# tr2.net
KiCad netlist of a schematic drawn in EAGLE
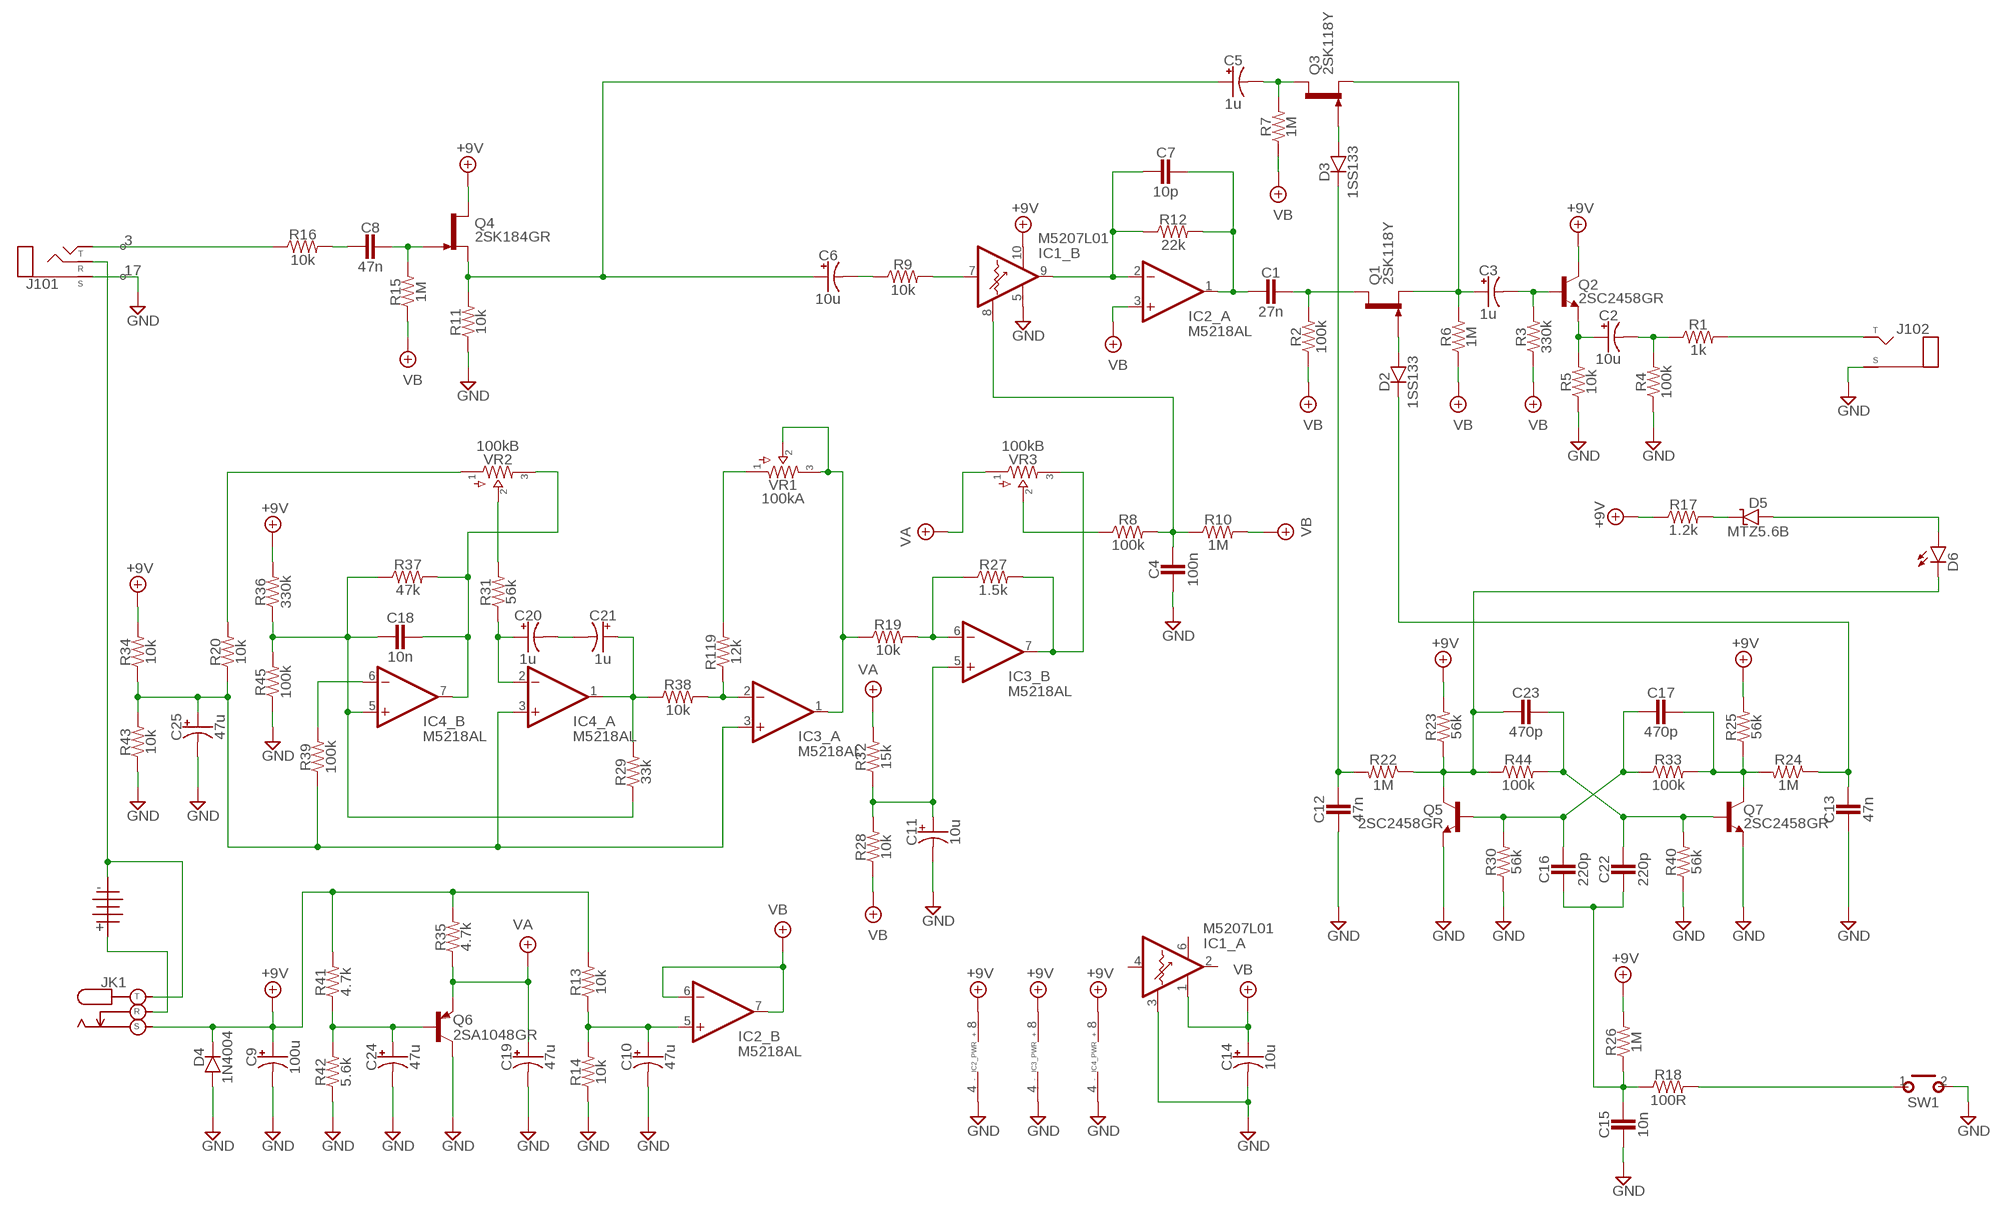
[diagram p0: schematic, sheet 1]

(export (version "E")
  (design (tool "Eeschema 10.0.6"))
  (components
    (comp (ref "1101")
      (value "BATTERY")
      (footprint "eagle-import:TWO_PADS")
      (libsource (lib "eagle-import") (part "BATTERY"))
    )
    (comp (ref "C1")
      (value "27n")
      (footprint "eagle-import:BOX_SMALL")
      (libsource (lib "eagle-import") (part "CER/FILMBOX.1"))
    )
    (comp (ref "C2")
      (value "10u")
      (footprint "eagle-import:040_020")
      (libsource (lib "eagle-import") (part "0400"))
    )
    (comp (ref "C3")
      (value "1u")
      (footprint "eagle-import:040_020")
      (libsource (lib "eagle-import") (part "0400"))
    )
    (comp (ref "C4")
      (value "100n")
      (footprint "eagle-import:BOX_SMALL")
      (libsource (lib "eagle-import") (part "CER/FILMBOX.1"))
    )
    (comp (ref "C5")
      (value "1u")
      (footprint "eagle-import:040_020")
      (libsource (lib "eagle-import") (part "0400"))
    )
    (comp (ref "C6")
      (value "10u")
      (footprint "eagle-import:040_020")
      (libsource (lib "eagle-import") (part "0400"))
    )
    (comp (ref "C7")
      (value "10p")
      (footprint "eagle-import:BOX_SMALL")
      (libsource (lib "eagle-import") (part "CER/FILMBOX.1"))
    )
    (comp (ref "C8")
      (value "47n")
      (footprint "eagle-import:BOX_SMALL")
      (libsource (lib "eagle-import") (part "CER/FILMBOX.1"))
    )
    (comp (ref "C9")
      (value "100u")
      (footprint "eagle-import:040_020")
      (libsource (lib "eagle-import") (part "0400"))
    )
    (comp (ref "C10")
      (value "47u")
      (footprint "eagle-import:040_020")
      (libsource (lib "eagle-import") (part "0400"))
    )
    (comp (ref "C11")
      (value "10u")
      (footprint "eagle-import:040_020")
      (libsource (lib "eagle-import") (part "0400"))
    )
    (comp (ref "C12")
      (value "47n")
      (footprint "eagle-import:BOX_SMALL")
      (libsource (lib "eagle-import") (part "CER/FILMBOX.1"))
    )
    (comp (ref "C13")
      (value "47n")
      (footprint "eagle-import:BOX_SMALL")
      (libsource (lib "eagle-import") (part "CER/FILMBOX.1"))
    )
    (comp (ref "C14")
      (value "10u")
      (footprint "eagle-import:040_020")
      (libsource (lib "eagle-import") (part "0400"))
    )
    (comp (ref "C15")
      (value "10n")
      (footprint "eagle-import:BOX_SMALL")
      (libsource (lib "eagle-import") (part "CER/FILMBOX.1"))
    )
    (comp (ref "C16")
      (value "220p")
      (footprint "eagle-import:BOX_SMALL")
      (libsource (lib "eagle-import") (part "CER/FILMBOX.1"))
    )
    (comp (ref "C17")
      (value "470p")
      (footprint "eagle-import:BOX_SMALL")
      (libsource (lib "eagle-import") (part "CER/FILMBOX.1"))
    )
    (comp (ref "C18")
      (value "10n")
      (footprint "eagle-import:BOX_SMALL")
      (libsource (lib "eagle-import") (part "CER/FILMBOX.1"))
    )
    (comp (ref "C19")
      (value "47u")
      (footprint "eagle-import:040_020")
      (libsource (lib "eagle-import") (part "0400"))
    )
    (comp (ref "C20")
      (value "1u")
      (footprint "eagle-import:040_020")
      (libsource (lib "eagle-import") (part "0400"))
    )
    (comp (ref "C21")
      (value "1u")
      (footprint "eagle-import:040_020")
      (libsource (lib "eagle-import") (part "0400"))
    )
    (comp (ref "C22")
      (value "220p")
      (footprint "eagle-import:BOX_SMALL")
      (libsource (lib "eagle-import") (part "CER/FILMBOX.1"))
    )
    (comp (ref "C23")
      (value "470p")
      (footprint "eagle-import:BOX_SMALL")
      (libsource (lib "eagle-import") (part "CER/FILMBOX.1"))
    )
    (comp (ref "C24")
      (value "47u")
      (footprint "eagle-import:040_020")
      (libsource (lib "eagle-import") (part "0400"))
    )
    (comp (ref "C25")
      (value "47u")
      (footprint "eagle-import:040_020")
      (libsource (lib "eagle-import") (part "0400"))
    )
    (comp (ref "D2")
      (value "1SS133")
      (footprint "eagle-import:DO35-2")
      (libsource (lib "eagle-import") (part "DO35.2"))
    )
    (comp (ref "D3")
      (value "1SS133")
      (footprint "eagle-import:DO35-2")
      (libsource (lib "eagle-import") (part "DO35.2"))
    )
    (comp (ref "D4")
      (value "1N4004")
      (footprint "eagle-import:DO35-2")
      (libsource (lib "eagle-import") (part "DO35.2"))
    )
    (comp (ref "D5")
      (value "MTZ5.6B")
      (footprint "eagle-import:DO41-2")
      (libsource (lib "eagle-import") (part "ZENER.2"))
    )
    (comp (ref "D6")
      (value "LN-28RP")
      (footprint "eagle-import:3MM_D")
      (libsource (lib "eagle-import") (part "LED"))
    )
    (comp (ref "IC1")
      (value "M5207L01")
      (footprint "eagle-import:SIL10")
      (libsource (lib "eagle-import") (part "M5207L01"))
    )
    (comp (ref "IC2")
      (value "M5218AL")
      (footprint "eagle-import:DIL0")
      (libsource (lib "eagle-import") (part "DUALTH"))
    )
    (comp (ref "IC3")
      (value "M5218AL")
      (footprint "eagle-import:DIL0")
      (libsource (lib "eagle-import") (part "DUALTH"))
    )
    (comp (ref "IC4")
      (value "M5218AL")
      (footprint "eagle-import:DIL0")
      (libsource (lib "eagle-import") (part "DUALTH"))
    )
    (comp (ref "J101")
      (value "STEREO3PADS")
      (footprint "eagle-import:THREEPADS")
      (libsource (lib "eagle-import") (part "STEREO3PADS"))
    )
    (comp (ref "J102")
      (value "MONO")
      (footprint "eagle-import:TWO_PADS")
      (libsource (lib "eagle-import") (part "MONO"))
    )
    (comp (ref "JK1")
      (value "DC_KOBICONN")
      (footprint "eagle-import:DC_KOBICONN")
      (libsource (lib "eagle-import") (part "DC_KOBICONN"))
    )
    (comp (ref "Q1")
      (value "2SK118Y")
      (footprint "eagle-import:TO92-")
      (libsource (lib "eagle-import") (part "2N3819TO-92S"))
    )
    (comp (ref "Q2")
      (value "2SC2458GR")
      (footprint "eagle-import:TO92-")
      (libsource (lib "eagle-import") (part "2SC828A"))
    )
    (comp (ref "Q3")
      (value "2SK118Y")
      (footprint "eagle-import:TO92-")
      (libsource (lib "eagle-import") (part "2N3819TO-92S"))
    )
    (comp (ref "Q4")
      (value "2SK184GR")
      (footprint "eagle-import:TO92-")
      (libsource (lib "eagle-import") (part "2N3819TO-92S"))
    )
    (comp (ref "Q5")
      (value "2SC2458GR")
      (footprint "eagle-import:TO92-")
      (libsource (lib "eagle-import") (part "2SC828A"))
    )
    (comp (ref "Q6")
      (value "2SA1048GR")
      (footprint "eagle-import:TO92-")
      (libsource (lib "eagle-import") (part "2N3906-"))
    )
    (comp (ref "Q7")
      (value "2SC2458GR")
      (footprint "eagle-import:TO92-")
      (libsource (lib "eagle-import") (part "2SC828A"))
    )
    (comp (ref "R1")
      (value "1k")
      (footprint "eagle-import:R0207_3")
      (libsource (lib "eagle-import") (part "R_.3B"))
    )
    (comp (ref "R2")
      (value "100k")
      (footprint "eagle-import:R0207_3")
      (libsource (lib "eagle-import") (part "R_.3B"))
    )
    (comp (ref "R3")
      (value "330k")
      (footprint "eagle-import:R0207_3")
      (libsource (lib "eagle-import") (part "R_.3B"))
    )
    (comp (ref "R4")
      (value "100k")
      (footprint "eagle-import:R0207_3")
      (libsource (lib "eagle-import") (part "R_.3B"))
    )
    (comp (ref "R5")
      (value "10k")
      (footprint "eagle-import:R0207_3")
      (libsource (lib "eagle-import") (part "R_.3B"))
    )
    (comp (ref "R6")
      (value "1M")
      (footprint "eagle-import:R0207_3")
      (libsource (lib "eagle-import") (part "R_.3B"))
    )
    (comp (ref "R7")
      (value "1M")
      (footprint "eagle-import:R0207_3")
      (libsource (lib "eagle-import") (part "R_.3B"))
    )
    (comp (ref "R8")
      (value "100k")
      (footprint "eagle-import:R0207_3")
      (libsource (lib "eagle-import") (part "R_.3B"))
    )
    (comp (ref "R9")
      (value "10k")
      (footprint "eagle-import:R0207_3")
      (libsource (lib "eagle-import") (part "R_.3B"))
    )
    (comp (ref "R10")
      (value "1M")
      (footprint "eagle-import:R0207_3")
      (libsource (lib "eagle-import") (part "R_.3B"))
    )
    (comp (ref "R11")
      (value "10k")
      (footprint "eagle-import:R0207_3")
      (libsource (lib "eagle-import") (part "R_.3B"))
    )
    (comp (ref "R12")
      (value "22k")
      (footprint "eagle-import:R0207_3")
      (libsource (lib "eagle-import") (part "R_.3B"))
    )
    (comp (ref "R13")
      (value "10k")
      (footprint "eagle-import:R0207_3")
      (libsource (lib "eagle-import") (part "R_.3B"))
    )
    (comp (ref "R14")
      (value "10k")
      (footprint "eagle-import:R0207_3")
      (libsource (lib "eagle-import") (part "R_.3B"))
    )
    (comp (ref "R15")
      (value "1M")
      (footprint "eagle-import:R0207_3")
      (libsource (lib "eagle-import") (part "R_.3B"))
    )
    (comp (ref "R16")
      (value "10k")
      (footprint "eagle-import:R0207_3")
      (libsource (lib "eagle-import") (part "R_.3B"))
    )
    (comp (ref "R17")
      (value "1.2k")
      (footprint "eagle-import:R0207_3")
      (libsource (lib "eagle-import") (part "R_.3B"))
    )
    (comp (ref "R18")
      (value "100R")
      (footprint "eagle-import:R0207_3")
      (libsource (lib "eagle-import") (part "R_.3B"))
    )
    (comp (ref "R19")
      (value "10k")
      (footprint "eagle-import:R0207_3")
      (libsource (lib "eagle-import") (part "R_.3B"))
    )
    (comp (ref "R20")
      (value "10k")
      (footprint "eagle-import:R0207_3")
      (libsource (lib "eagle-import") (part "R_.3B"))
    )
    (comp (ref "R22")
      (value "1M")
      (footprint "eagle-import:R0207_3")
      (libsource (lib "eagle-import") (part "R_.3B"))
    )
    (comp (ref "R23")
      (value "56k")
      (footprint "eagle-import:R0207_3")
      (libsource (lib "eagle-import") (part "R_.3B"))
    )
    (comp (ref "R24")
      (value "1M")
      (footprint "eagle-import:R0207_3")
      (libsource (lib "eagle-import") (part "R_.3B"))
    )
    (comp (ref "R25")
      (value "56k")
      (footprint "eagle-import:R0207_3")
      (libsource (lib "eagle-import") (part "R_.3B"))
    )
    (comp (ref "R26")
      (value "1M")
      (footprint "eagle-import:R0207_3")
      (libsource (lib "eagle-import") (part "R_.3B"))
    )
    (comp (ref "R27")
      (value "1.5k")
      (footprint "eagle-import:R0207_3")
      (libsource (lib "eagle-import") (part "R_.3B"))
    )
    (comp (ref "R28")
      (value "10k")
      (footprint "eagle-import:R0207_3")
      (libsource (lib "eagle-import") (part "R_.3B"))
    )
    (comp (ref "R29")
      (value "33k")
      (footprint "eagle-import:R0207_3")
      (libsource (lib "eagle-import") (part "R_.3B"))
    )
    (comp (ref "R30")
      (value "56k")
      (footprint "eagle-import:R0207_3")
      (libsource (lib "eagle-import") (part "R_.3B"))
    )
    (comp (ref "R31")
      (value "56k")
      (footprint "eagle-import:R0207_3")
      (libsource (lib "eagle-import") (part "R_.3B"))
    )
    (comp (ref "R32")
      (value "15k")
      (footprint "eagle-import:R0207_3")
      (libsource (lib "eagle-import") (part "R_.3B"))
    )
    (comp (ref "R33")
      (value "100k")
      (footprint "eagle-import:R0207_3")
      (libsource (lib "eagle-import") (part "R_.3B"))
    )
    (comp (ref "R34")
      (value "10k")
      (footprint "eagle-import:R0207_3")
      (libsource (lib "eagle-import") (part "R_.3B"))
    )
    (comp (ref "R35")
      (value "4.7k")
      (footprint "eagle-import:R0207_3")
      (libsource (lib "eagle-import") (part "R_.3B"))
    )
    (comp (ref "R36")
      (value "330k")
      (footprint "eagle-import:R0207_3")
      (libsource (lib "eagle-import") (part "R_.3B"))
    )
    (comp (ref "R37")
      (value "47k")
      (footprint "eagle-import:R0207_3")
      (libsource (lib "eagle-import") (part "R_.3B"))
    )
    (comp (ref "R38")
      (value "10k")
      (footprint "eagle-import:R0207_3")
      (libsource (lib "eagle-import") (part "R_.3B"))
    )
    (comp (ref "R39")
      (value "100k")
      (footprint "eagle-import:R0207_3")
      (libsource (lib "eagle-import") (part "R_.3B"))
    )
    (comp (ref "R40")
      (value "56k")
      (footprint "eagle-import:R0207_3")
      (libsource (lib "eagle-import") (part "R_.3B"))
    )
    (comp (ref "R41")
      (value "4.7k")
      (footprint "eagle-import:R0207_3")
      (libsource (lib "eagle-import") (part "R_.3B"))
    )
    (comp (ref "R42")
      (value "5.6k")
      (footprint "eagle-import:R0207_3")
      (libsource (lib "eagle-import") (part "R_.3B"))
    )
    (comp (ref "R43")
      (value "10k")
      (footprint "eagle-import:R0207_3")
      (libsource (lib "eagle-import") (part "R_.3B"))
    )
    (comp (ref "R44")
      (value "100k")
      (footprint "eagle-import:R0207_3")
      (libsource (lib "eagle-import") (part "R_.3B"))
    )
    (comp (ref "R45")
      (value "100k")
      (footprint "eagle-import:R0207_3")
      (libsource (lib "eagle-import") (part "R_.3B"))
    )
    (comp (ref "R119")
      (value "12k")
      (footprint "eagle-import:R0207_3")
      (libsource (lib "eagle-import") (part "R_.3B"))
    )
    (comp (ref "SW1")
      (value "MOMENTARY")
      (footprint "eagle-import:SPST")
      (libsource (lib "eagle-import") (part "MOMENTARY"))
    )
    (comp (ref "VR1")
      (value "100kA")
      (footprint "eagle-import:16MM")
      (libsource (lib "eagle-import") (part "POTS16MM"))
    )
    (comp (ref "VR2")
      (value "100kB")
      (footprint "eagle-import:16MM")
      (libsource (lib "eagle-import") (part "POTS16MM"))
    )
    (comp (ref "VR3")
      (value "100kB")
      (footprint "eagle-import:16MM")
      (libsource (lib "eagle-import") (part "POTS16MM"))
    )
  )
  (nets
    (net (code "1") (name "+9V") (class "Default")
      (node (ref "C9") (pin "+") (pinfunction "+_+") (pintype "passive"))
      (node (ref "D4") (pin "C") (pinfunction "C_C") (pintype "passive"))
      (node (ref "IC1") (pin "10") (pinfunction "+PWR_10") (pintype "power_in"))
      (node (ref "IC2") (pin "8") (pinfunction "V+_8") (pintype "power_in"))
      (node (ref "IC3") (pin "8") (pinfunction "V+_8") (pintype "power_in"))
      (node (ref "IC4") (pin "8") (pinfunction "V+_8") (pintype "power_in"))
      (node (ref "JK1") (pin "S") (pinfunction "S_S") (pintype "bidirectional"))
      (node (ref "Q2") (pin "2") (pinfunction "C_2") (pintype "passive"))
      (node (ref "Q4") (pin "3") (pinfunction "D_3") (pintype "passive"))
      (node (ref "R13") (pin "2") (pinfunction "2_2") (pintype "passive"))
      (node (ref "R17") (pin "1") (pinfunction "1_1") (pintype "passive"))
      (node (ref "R23") (pin "2") (pinfunction "2_2") (pintype "passive"))
      (node (ref "R25") (pin "2") (pinfunction "2_2") (pintype "passive"))
      (node (ref "R26") (pin "2") (pinfunction "2_2") (pintype "passive"))
      (node (ref "R34") (pin "2") (pinfunction "2_2") (pintype "passive"))
      (node (ref "R35") (pin "2") (pinfunction "2_2") (pintype "passive"))
      (node (ref "R36") (pin "2") (pinfunction "2_2") (pintype "passive"))
      (node (ref "R41") (pin "2") (pinfunction "2_2") (pintype "passive"))
    )
    (net (code "2") (name "/+PWR") (class "Default")
      (node (ref "IC1") (pin "6") (pinfunction "+PWR_6") (pintype "power_in"))
    )
    (net (code "3") (name "GND") (class "Default")
      (node (ref "C10") (pin "-") (pinfunction "-_-") (pintype "passive"))
      (node (ref "C11") (pin "-") (pinfunction "-_-") (pintype "passive"))
      (node (ref "C12") (pin "2") (pinfunction "2_2") (pintype "passive"))
      (node (ref "C13") (pin "2") (pinfunction "2_2") (pintype "passive"))
      (node (ref "C14") (pin "-") (pinfunction "-_-") (pintype "passive"))
      (node (ref "C15") (pin "2") (pinfunction "2_2") (pintype "passive"))
      (node (ref "C19") (pin "-") (pinfunction "-_-") (pintype "passive"))
      (node (ref "C24") (pin "-") (pinfunction "-_-") (pintype "passive"))
      (node (ref "C25") (pin "-") (pinfunction "-_-") (pintype "passive"))
      (node (ref "C4") (pin "2") (pinfunction "2_2") (pintype "passive"))
      (node (ref "C9") (pin "-") (pinfunction "-_-") (pintype "passive"))
      (node (ref "D4") (pin "A") (pinfunction "A_A") (pintype "passive"))
      (node (ref "IC1") (pin "3") (pinfunction "VC_3") (pintype "bidirectional"))
      (node (ref "IC1") (pin "5") (pinfunction "-PWR_5") (pintype "power_in"))
      (node (ref "IC2") (pin "4") (pinfunction "V-_4") (pintype "power_in"))
      (node (ref "IC3") (pin "4") (pinfunction "V-_4") (pintype "power_in"))
      (node (ref "IC4") (pin "4") (pinfunction "V-_4") (pintype "power_in"))
      (node (ref "J101") (pin "SLEEVE") (pinfunction "S_SLEEVE") (pintype "passive"))
      (node (ref "J102") (pin "S") (pinfunction "SLEEVE_S") (pintype "passive"))
      (node (ref "Q5") (pin "3") (pinfunction "E_3") (pintype "passive"))
      (node (ref "Q6") (pin "1") (pinfunction "C_1") (pintype "passive"))
      (node (ref "Q7") (pin "3") (pinfunction "E_3") (pintype "passive"))
      (node (ref "R11") (pin "1") (pinfunction "1_1") (pintype "passive"))
      (node (ref "R14") (pin "1") (pinfunction "1_1") (pintype "passive"))
      (node (ref "R30") (pin "1") (pinfunction "1_1") (pintype "passive"))
      (node (ref "R4") (pin "1") (pinfunction "1_1") (pintype "passive"))
      (node (ref "R40") (pin "1") (pinfunction "1_1") (pintype "passive"))
      (node (ref "R42") (pin "1") (pinfunction "1_1") (pintype "passive"))
      (node (ref "R43") (pin "1") (pinfunction "1_1") (pintype "passive"))
      (node (ref "R45") (pin "1") (pinfunction "1_1") (pintype "passive"))
      (node (ref "R5") (pin "1") (pinfunction "1_1") (pintype "passive"))
      (node (ref "SW1") (pin "2") (pinfunction "S_2") (pintype "passive"))
    )
    (net (code "4") (name "Net-(1101-P$1)") (class "Default")
      (node (ref "1101") (pin "T") (pinfunction "P$1_T") (pintype "bidirectional"))
      (node (ref "JK1") (pin "R") (pinfunction "R_R") (pintype "bidirectional"))
    )
    (net (code "5") (name "Net-(1101-P$2)") (class "Default")
      (node (ref "1101") (pin "S") (pinfunction "P$2_S") (pintype "bidirectional"))
      (node (ref "J101") (pin "RING") (pinfunction "R_RING") (pintype "passive"))
      (node (ref "JK1") (pin "T") (pinfunction "T_T") (pintype "bidirectional"))
    )
    (net (code "6") (name "Net-(C2-Pad-)") (class "Default")
      (node (ref "C2") (pin "-") (pinfunction "-_-") (pintype "passive"))
      (node (ref "R1") (pin "1") (pinfunction "1_1") (pintype "passive"))
      (node (ref "R4") (pin "2") (pinfunction "2_2") (pintype "passive"))
    )
    (net (code "7") (name "Net-(C6-Pad-)") (class "Default")
      (node (ref "C6") (pin "-") (pinfunction "-_-") (pintype "passive"))
      (node (ref "R9") (pin "1") (pinfunction "1_1") (pintype "passive"))
    )
    (net (code "8") (name "Net-(C8-Pad2)") (class "Default")
      (node (ref "C8") (pin "2") (pinfunction "2_2") (pintype "passive"))
      (node (ref "R16") (pin "2") (pinfunction "2_2") (pintype "passive"))
    )
    (net (code "9") (name "Net-(C12-Pad1)") (class "Default")
      (node (ref "C12") (pin "1") (pinfunction "1_1") (pintype "passive"))
      (node (ref "D3") (pin "C") (pinfunction "C_C") (pintype "passive"))
      (node (ref "R22") (pin "2") (pinfunction "2_2") (pintype "passive"))
    )
    (net (code "10") (name "Net-(C13-Pad1)") (class "Default")
      (node (ref "C13") (pin "1") (pinfunction "1_1") (pintype "passive"))
      (node (ref "D2") (pin "C") (pinfunction "C_C") (pintype "passive"))
      (node (ref "R24") (pin "1") (pinfunction "1_1") (pintype "passive"))
    )
    (net (code "11") (name "Net-(C15-Pad1)") (class "Default")
      (node (ref "C15") (pin "1") (pinfunction "1_1") (pintype "passive"))
      (node (ref "C16") (pin "2") (pinfunction "2_2") (pintype "passive"))
      (node (ref "C22") (pin "2") (pinfunction "2_2") (pintype "passive"))
      (node (ref "R18") (pin "1") (pinfunction "1_1") (pintype "passive"))
      (node (ref "R26") (pin "1") (pinfunction "1_1") (pintype "passive"))
    )
    (net (code "12") (name "Net-(C20-Pad-)") (class "Default")
      (node (ref "C20") (pin "-") (pinfunction "-_-") (pintype "passive"))
      (node (ref "C21") (pin "-") (pinfunction "-_-") (pintype "passive"))
    )
    (net (code "13") (name "Net-(D5-PadC)") (class "Default")
      (node (ref "D5") (pin "C") (pinfunction "C_C") (pintype "passive"))
      (node (ref "R17") (pin "2") (pinfunction "2_2") (pintype "passive"))
    )
    (net (code "14") (name "Net-(D6-A)") (class "Default")
      (node (ref "D5") (pin "A") (pinfunction "A_A") (pintype "passive"))
      (node (ref "D6") (pin "ANODE") (pinfunction "A_ANODE") (pintype "passive"))
    )
    (net (code "15") (name "Net-(D6-C)") (class "Default")
      (node (ref "C23") (pin "2") (pinfunction "2_2") (pintype "passive"))
      (node (ref "D6") (pin "P$1") (pinfunction "C_P$1") (pintype "passive"))
      (node (ref "Q5") (pin "2") (pinfunction "C_2") (pintype "passive"))
      (node (ref "R22") (pin "1") (pinfunction "1_1") (pintype "passive"))
      (node (ref "R23") (pin "1") (pinfunction "1_1") (pintype "passive"))
      (node (ref "R44") (pin "1") (pinfunction "1_1") (pintype "passive"))
    )
    (net (code "16") (name "Net-(IC1B-IN)") (class "Default")
      (node (ref "IC1") (pin "7") (pinfunction "IN_7") (pintype "input"))
      (node (ref "R9") (pin "2") (pinfunction "2_2") (pintype "passive"))
    )
    (net (code "17") (name "Net-(IC1B-OUT)") (class "Default")
      (node (ref "C7") (pin "2") (pinfunction "2_2") (pintype "passive"))
      (node (ref "IC1") (pin "9") (pinfunction "OUT_9") (pintype "output"))
      (node (ref "IC2") (pin "2") (pinfunction "-IN_2") (pintype "input"))
      (node (ref "R12") (pin "1") (pinfunction "1_1") (pintype "passive"))
    )
    (net (code "18") (name "Net-(IC1B-VC)") (class "Default")
      (node (ref "C4") (pin "1") (pinfunction "1_1") (pintype "passive"))
      (node (ref "IC1") (pin "8") (pinfunction "VC_8") (pintype "bidirectional"))
      (node (ref "R10") (pin "1") (pinfunction "1_1") (pintype "passive"))
      (node (ref "R8") (pin "2") (pinfunction "2_2") (pintype "passive"))
    )
    (net (code "19") (name "Net-(IC2A-OUT)") (class "Default")
      (node (ref "C1") (pin "2") (pinfunction "2_2") (pintype "passive"))
      (node (ref "C7") (pin "1") (pinfunction "1_1") (pintype "passive"))
      (node (ref "IC2") (pin "1") (pinfunction "OUT_1") (pintype "output"))
      (node (ref "R12") (pin "2") (pinfunction "2_2") (pintype "passive"))
    )
    (net (code "20") (name "Net-(IC2B-+IN)") (class "Default")
      (node (ref "C10") (pin "+") (pinfunction "+_+") (pintype "passive"))
      (node (ref "IC2") (pin "5") (pinfunction "+IN_5") (pintype "input"))
      (node (ref "R13") (pin "1") (pinfunction "1_1") (pintype "passive"))
      (node (ref "R14") (pin "2") (pinfunction "2_2") (pintype "passive"))
    )
    (net (code "21") (name "Net-(IC3A-+IN)") (class "Default")
      (node (ref "C25") (pin "+") (pinfunction "+_+") (pintype "passive"))
      (node (ref "IC3") (pin "3") (pinfunction "+IN_3") (pintype "input"))
      (node (ref "IC4") (pin "3") (pinfunction "+IN_3") (pintype "input"))
      (node (ref "R20") (pin "1") (pinfunction "1_1") (pintype "passive"))
      (node (ref "R34") (pin "1") (pinfunction "1_1") (pintype "passive"))
      (node (ref "R39") (pin "1") (pinfunction "1_1") (pintype "passive"))
      (node (ref "R43") (pin "2") (pinfunction "2_2") (pintype "passive"))
    )
    (net (code "22") (name "Net-(IC3A--IN)") (class "Default")
      (node (ref "IC3") (pin "2") (pinfunction "-IN_2") (pintype "input"))
      (node (ref "R119") (pin "1") (pinfunction "1_1") (pintype "passive"))
      (node (ref "R38") (pin "2") (pinfunction "2_2") (pintype "passive"))
    )
    (net (code "23") (name "Net-(IC3A-OUT)") (class "Default")
      (node (ref "IC3") (pin "1") (pinfunction "OUT_1") (pintype "output"))
      (node (ref "R19") (pin "1") (pinfunction "1_1") (pintype "passive"))
      (node (ref "VR1") (pin "2") (pinfunction "2_2") (pintype "passive"))
      (node (ref "VR1") (pin "3") (pinfunction "3_3") (pintype "passive"))
    )
    (net (code "24") (name "Net-(IC3B-+IN)") (class "Default")
      (node (ref "C11") (pin "+") (pinfunction "+_+") (pintype "passive"))
      (node (ref "IC3") (pin "5") (pinfunction "+IN_5") (pintype "input"))
      (node (ref "R28") (pin "2") (pinfunction "2_2") (pintype "passive"))
      (node (ref "R32") (pin "1") (pinfunction "1_1") (pintype "passive"))
    )
    (net (code "25") (name "Net-(IC3B--IN)") (class "Default")
      (node (ref "IC3") (pin "6") (pinfunction "-IN_6") (pintype "input"))
      (node (ref "R19") (pin "2") (pinfunction "2_2") (pintype "passive"))
      (node (ref "R27") (pin "1") (pinfunction "1_1") (pintype "passive"))
    )
    (net (code "26") (name "Net-(IC3B-OUT)") (class "Default")
      (node (ref "IC3") (pin "7") (pinfunction "OUT_7") (pintype "output"))
      (node (ref "R27") (pin "2") (pinfunction "2_2") (pintype "passive"))
      (node (ref "VR3") (pin "3") (pinfunction "3_3") (pintype "passive"))
    )
    (net (code "27") (name "Net-(IC4A--IN)") (class "Default")
      (node (ref "C20") (pin "+") (pinfunction "+_+") (pintype "passive"))
      (node (ref "IC4") (pin "2") (pinfunction "-IN_2") (pintype "input"))
      (node (ref "R31") (pin "1") (pinfunction "1_1") (pintype "passive"))
    )
    (net (code "28") (name "Net-(IC4A-OUT)") (class "Default")
      (node (ref "C21") (pin "+") (pinfunction "+_+") (pintype "passive"))
      (node (ref "IC4") (pin "1") (pinfunction "OUT_1") (pintype "output"))
      (node (ref "R29") (pin "2") (pinfunction "2_2") (pintype "passive"))
      (node (ref "R38") (pin "1") (pinfunction "1_1") (pintype "passive"))
    )
    (net (code "29") (name "Net-(IC4B-+IN)") (class "Default")
      (node (ref "C18") (pin "2") (pinfunction "2_2") (pintype "passive"))
      (node (ref "IC4") (pin "5") (pinfunction "+IN_5") (pintype "input"))
      (node (ref "R29") (pin "1") (pinfunction "1_1") (pintype "passive"))
      (node (ref "R36") (pin "1") (pinfunction "1_1") (pintype "passive"))
      (node (ref "R37") (pin "1") (pinfunction "1_1") (pintype "passive"))
      (node (ref "R45") (pin "2") (pinfunction "2_2") (pintype "passive"))
    )
    (net (code "30") (name "Net-(IC4B--IN)") (class "Default")
      (node (ref "IC4") (pin "6") (pinfunction "-IN_6") (pintype "input"))
      (node (ref "R39") (pin "2") (pinfunction "2_2") (pintype "passive"))
    )
    (net (code "31") (name "Net-(IC4B-OUT)") (class "Default")
      (node (ref "C18") (pin "1") (pinfunction "1_1") (pintype "passive"))
      (node (ref "IC4") (pin "7") (pinfunction "OUT_7") (pintype "output"))
      (node (ref "R37") (pin "2") (pinfunction "2_2") (pintype "passive"))
      (node (ref "VR2") (pin "3") (pinfunction "3_3") (pintype "passive"))
    )
    (net (code "32") (name "Net-(J101-T)") (class "Default")
      (node (ref "J101") (pin "TIP") (pinfunction "T_TIP") (pintype "passive"))
      (node (ref "R16") (pin "1") (pinfunction "1_1") (pintype "passive"))
    )
    (net (code "33") (name "Net-(J102-TIP)") (class "Default")
      (node (ref "J102") (pin "T") (pinfunction "TIP_T") (pintype "passive"))
      (node (ref "R1") (pin "2") (pinfunction "2_2") (pintype "passive"))
    )
    (net (code "34") (name "Net-(Q1-D)") (class "Default")
      (node (ref "C1") (pin "1") (pinfunction "1_1") (pintype "passive"))
      (node (ref "Q1") (pin "3") (pinfunction "D_3") (pintype "passive"))
      (node (ref "R2") (pin "2") (pinfunction "2_2") (pintype "passive"))
    )
    (net (code "35") (name "Net-(Q1-G)") (class "Default")
      (node (ref "D2") (pin "A") (pinfunction "A_A") (pintype "passive"))
      (node (ref "Q1") (pin "2") (pinfunction "G_2") (pintype "passive"))
    )
    (net (code "36") (name "Net-(Q1-S)") (class "Default")
      (node (ref "C3") (pin "+") (pinfunction "+_+") (pintype "passive"))
      (node (ref "Q1") (pin "1") (pinfunction "S_1") (pintype "passive"))
      (node (ref "Q3") (pin "1") (pinfunction "S_1") (pintype "passive"))
      (node (ref "R6") (pin "2") (pinfunction "2_2") (pintype "passive"))
    )
    (net (code "37") (name "Net-(Q2-B)") (class "Default")
      (node (ref "C3") (pin "-") (pinfunction "-_-") (pintype "passive"))
      (node (ref "Q2") (pin "1") (pinfunction "B_1") (pintype "passive"))
      (node (ref "R3") (pin "2") (pinfunction "2_2") (pintype "passive"))
    )
    (net (code "38") (name "Net-(Q2-E)") (class "Default")
      (node (ref "C2") (pin "+") (pinfunction "+_+") (pintype "passive"))
      (node (ref "Q2") (pin "3") (pinfunction "E_3") (pintype "passive"))
      (node (ref "R5") (pin "2") (pinfunction "2_2") (pintype "passive"))
    )
    (net (code "39") (name "Net-(Q3-D)") (class "Default")
      (node (ref "C5") (pin "-") (pinfunction "-_-") (pintype "passive"))
      (node (ref "Q3") (pin "3") (pinfunction "D_3") (pintype "passive"))
      (node (ref "R7") (pin "2") (pinfunction "2_2") (pintype "passive"))
    )
    (net (code "40") (name "Net-(Q3-G)") (class "Default")
      (node (ref "D3") (pin "A") (pinfunction "A_A") (pintype "passive"))
      (node (ref "Q3") (pin "2") (pinfunction "G_2") (pintype "passive"))
    )
    (net (code "41") (name "Net-(Q4-G)") (class "Default")
      (node (ref "C8") (pin "1") (pinfunction "1_1") (pintype "passive"))
      (node (ref "Q4") (pin "2") (pinfunction "G_2") (pintype "passive"))
      (node (ref "R15") (pin "2") (pinfunction "2_2") (pintype "passive"))
    )
    (net (code "42") (name "Net-(Q4-S)") (class "Default")
      (node (ref "C5") (pin "+") (pinfunction "+_+") (pintype "passive"))
      (node (ref "C6") (pin "+") (pinfunction "+_+") (pintype "passive"))
      (node (ref "Q4") (pin "1") (pinfunction "S_1") (pintype "passive"))
      (node (ref "R11") (pin "2") (pinfunction "2_2") (pintype "passive"))
    )
    (net (code "43") (name "Net-(Q5-B)") (class "Default")
      (node (ref "C16") (pin "1") (pinfunction "1_1") (pintype "passive"))
      (node (ref "C17") (pin "2") (pinfunction "2_2") (pintype "passive"))
      (node (ref "Q5") (pin "1") (pinfunction "B_1") (pintype "passive"))
      (node (ref "R30") (pin "2") (pinfunction "2_2") (pintype "passive"))
      (node (ref "R33") (pin "1") (pinfunction "1_1") (pintype "passive"))
    )
    (net (code "44") (name "Net-(Q6-B)") (class "Default")
      (node (ref "C24") (pin "+") (pinfunction "+_+") (pintype "passive"))
      (node (ref "Q6") (pin "2") (pinfunction "B_2") (pintype "passive"))
      (node (ref "R41") (pin "1") (pinfunction "1_1") (pintype "passive"))
      (node (ref "R42") (pin "2") (pinfunction "2_2") (pintype "passive"))
    )
    (net (code "45") (name "Net-(Q7-B)") (class "Default")
      (node (ref "C22") (pin "1") (pinfunction "1_1") (pintype "passive"))
      (node (ref "C23") (pin "1") (pinfunction "1_1") (pintype "passive"))
      (node (ref "Q7") (pin "1") (pinfunction "B_1") (pintype "passive"))
      (node (ref "R40") (pin "2") (pinfunction "2_2") (pintype "passive"))
      (node (ref "R44") (pin "2") (pinfunction "2_2") (pintype "passive"))
    )
    (net (code "46") (name "Net-(Q7-C)") (class "Default")
      (node (ref "C17") (pin "1") (pinfunction "1_1") (pintype "passive"))
      (node (ref "Q7") (pin "2") (pinfunction "C_2") (pintype "passive"))
      (node (ref "R24") (pin "2") (pinfunction "2_2") (pintype "passive"))
      (node (ref "R25") (pin "1") (pinfunction "1_1") (pintype "passive"))
      (node (ref "R33") (pin "2") (pinfunction "2_2") (pintype "passive"))
    )
    (net (code "47") (name "Net-(R8-Pad1)") (class "Default")
      (node (ref "R8") (pin "1") (pinfunction "1_1") (pintype "passive"))
      (node (ref "VR3") (pin "2") (pinfunction "2_2") (pintype "passive"))
    )
    (net (code "48") (name "Net-(R20-Pad2)") (class "Default")
      (node (ref "R20") (pin "2") (pinfunction "2_2") (pintype "passive"))
      (node (ref "VR2") (pin "1") (pinfunction "1_1") (pintype "passive"))
    )
    (net (code "49") (name "Net-(R31-Pad2)") (class "Default")
      (node (ref "R31") (pin "2") (pinfunction "2_2") (pintype "passive"))
      (node (ref "VR2") (pin "2") (pinfunction "2_2") (pintype "passive"))
    )
    (net (code "50") (name "Net-(R119-Pad2)") (class "Default")
      (node (ref "R119") (pin "2") (pinfunction "2_2") (pintype "passive"))
      (node (ref "VR1") (pin "1") (pinfunction "1_1") (pintype "passive"))
    )
    (net (code "51") (name "Net-(SW1-P)") (class "Default")
      (node (ref "R18") (pin "2") (pinfunction "2_2") (pintype "passive"))
      (node (ref "SW1") (pin "1") (pinfunction "P_1") (pintype "passive"))
    )
    (net (code "52") (name "VA") (class "Default")
      (node (ref "C19") (pin "+") (pinfunction "+_+") (pintype "passive"))
      (node (ref "Q6") (pin "3") (pinfunction "E_3") (pintype "passive"))
      (node (ref "R32") (pin "2") (pinfunction "2_2") (pintype "passive"))
      (node (ref "R35") (pin "1") (pinfunction "1_1") (pintype "passive"))
      (node (ref "VR3") (pin "1") (pinfunction "1_1") (pintype "passive"))
    )
    (net (code "53") (name "VB") (class "Default")
      (node (ref "C14") (pin "+") (pinfunction "+_+") (pintype "passive"))
      (node (ref "IC1") (pin "1") (pinfunction "-PWR_1") (pintype "power_in"))
      (node (ref "IC2") (pin "3") (pinfunction "+IN_3") (pintype "input"))
      (node (ref "IC2") (pin "6") (pinfunction "-IN_6") (pintype "input"))
      (node (ref "IC2") (pin "7") (pinfunction "OUT_7") (pintype "output"))
      (node (ref "R10") (pin "2") (pinfunction "2_2") (pintype "passive"))
      (node (ref "R15") (pin "1") (pinfunction "1_1") (pintype "passive"))
      (node (ref "R2") (pin "1") (pinfunction "1_1") (pintype "passive"))
      (node (ref "R28") (pin "1") (pinfunction "1_1") (pintype "passive"))
      (node (ref "R3") (pin "1") (pinfunction "1_1") (pintype "passive"))
      (node (ref "R6") (pin "1") (pinfunction "1_1") (pintype "passive"))
      (node (ref "R7") (pin "1") (pinfunction "1_1") (pintype "passive"))
    )
    (net (code "54") (name "unconnected-(IC1A-IN-Pad4)") (class "Default")
      (node (ref "IC1") (pin "4") (pinfunction "IN_4") (pintype "input"))
    )
    (net (code "55") (name "unconnected-(IC1A-OUT-Pad2)") (class "Default")
      (node (ref "IC1") (pin "2") (pinfunction "OUT_2") (pintype "output"))
    )
  )
)
